# v3-landshark-handheld-controller.net
KiCad netlist of a schematic drawn in EAGLE
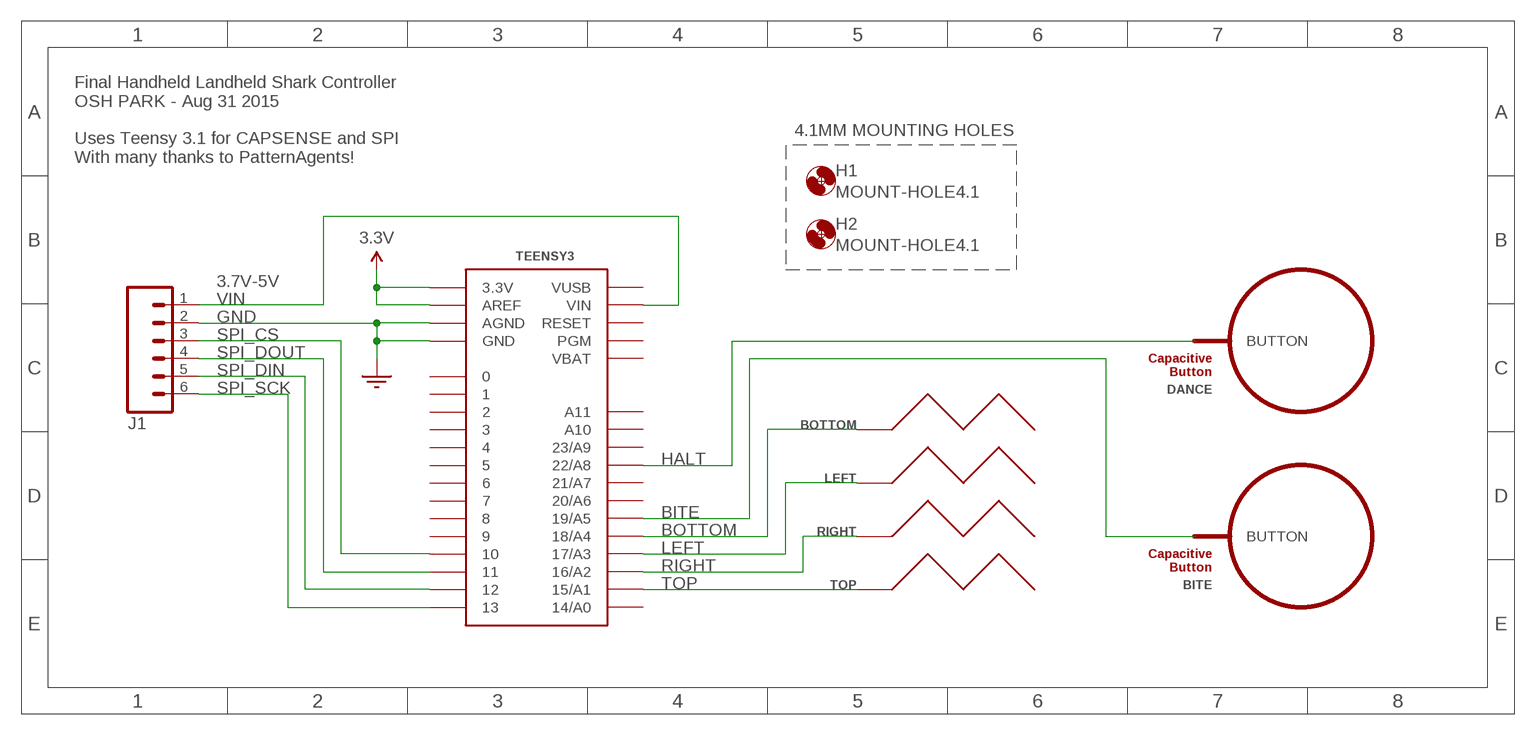
[diagram p0: schematic, sheet 1]

(export (version "E")
  (design (tool "Eeschema 10.0.6"))
  (components
    (comp (ref "BITE")
      (value "BUTTON_PASSIVE_12MM_BITE")
      (footprint "eagle-import:BUTTON_PASSIVE_12MM_BITE")
      (libsource (lib "eagle-import") (part "BUTTON_PASSIVE_12MM_BITE"))
    )
    (comp (ref "BOTTOM")
      (value "SLIDER_PASSIVE_1SEG")
      (footprint "eagle-import:SLIDER_PASSIVE_1SEG_12MM")
      (libsource (lib "eagle-import") (part "SLIDER_PASSIVE_1SEG"))
    )
    (comp (ref "DANCE")
      (value "BUTTON_PASSIVE_12MM_DANCE")
      (footprint "eagle-import:BUTTON_PASSIVE_12MM_DANCE")
      (libsource (lib "eagle-import") (part "BUTTON_PASSIVE_12MM_DANCE"))
    )
    (comp (ref "H1")
      (value "MOUNT-HOLE4.1")
      (footprint "eagle-import:4,1")
      (libsource (lib "eagle-import") (part "MOUNT-HOLE4.1"))
    )
    (comp (ref "H2")
      (value "MOUNT-HOLE4.1")
      (footprint "eagle-import:4,1")
      (libsource (lib "eagle-import") (part "MOUNT-HOLE4.1"))
    )
    (comp (ref "J1")
      (value "M06LOCK_LONGPADS")
      (footprint "eagle-import:1X06_LOCK_LONGPADS")
      (libsource (lib "eagle-import") (part "M06LOCK_LONGPADS"))
    )
    (comp (ref "LEFT")
      (value "SLIDER_PASSIVE_1SEG")
      (footprint "eagle-import:SLIDER_PASSIVE_1SEG_12MM")
      (libsource (lib "eagle-import") (part "SLIDER_PASSIVE_1SEG"))
    )
    (comp (ref "RIGHT")
      (value "SLIDER_PASSIVE_1SEG")
      (footprint "eagle-import:SLIDER_PASSIVE_1SEG_12MM")
      (libsource (lib "eagle-import") (part "SLIDER_PASSIVE_1SEG"))
    )
    (comp (ref "TEENSY3")
      (value "TEENSY_3.0+4")
      (footprint "eagle-import:TEENSY_3.0+4")
      (libsource (lib "eagle-import") (part "TEENSY_3.0+4"))
    )
    (comp (ref "TOP")
      (value "SLIDER_PASSIVE_1SEG")
      (footprint "eagle-import:SLIDER_PASSIVE_1SEG_12MM")
      (libsource (lib "eagle-import") (part "SLIDER_PASSIVE_1SEG"))
    )
  )
  (nets
    (net (code "1") (name "/BITE") (class "Default")
      (node (ref "BITE") (pin "BUTTON") (pinfunction "BUTTON_BUTTON") (pintype "passive"))
      (node (ref "TEENSY3") (pin "19/A5") (pinfunction "19/A5_19/A5") (pintype "bidirectional"))
    )
    (net (code "2") (name "/BOTTOM") (class "Default")
      (node (ref "BOTTOM") (pin "P$1") (pinfunction "SL1_P$1") (pintype "passive"))
      (node (ref "TEENSY3") (pin "18/A4") (pinfunction "18/A4_18/A4") (pintype "bidirectional"))
    )
    (net (code "3") (name "/HALT") (class "Default")
      (node (ref "DANCE") (pin "BUTTON") (pinfunction "BUTTON_BUTTON") (pintype "passive"))
      (node (ref "TEENSY3") (pin "22/A8") (pinfunction "22/A8_22/A8") (pintype "bidirectional"))
    )
    (net (code "4") (name "/LEFT") (class "Default")
      (node (ref "LEFT") (pin "P$1") (pinfunction "SL1_P$1") (pintype "passive"))
      (node (ref "TEENSY3") (pin "17/A3") (pinfunction "17/A3_17/A3") (pintype "bidirectional"))
    )
    (net (code "5") (name "/RIGHT") (class "Default")
      (node (ref "RIGHT") (pin "P$1") (pinfunction "SL1_P$1") (pintype "passive"))
      (node (ref "TEENSY3") (pin "16/A2") (pinfunction "16/A2_16/A2") (pintype "bidirectional"))
    )
    (net (code "6") (name "/SPI_CS") (class "Default")
      (node (ref "J1") (pin "3") (pinfunction "3_3") (pintype "passive"))
      (node (ref "TEENSY3") (pin "10") (pinfunction "10_10") (pintype "bidirectional"))
    )
    (net (code "7") (name "/SPI_DIN") (class "Default")
      (node (ref "J1") (pin "5") (pinfunction "5_5") (pintype "passive"))
      (node (ref "TEENSY3") (pin "12") (pinfunction "12_12") (pintype "bidirectional"))
    )
    (net (code "8") (name "/SPI_DOUT") (class "Default")
      (node (ref "J1") (pin "4") (pinfunction "4_4") (pintype "passive"))
      (node (ref "TEENSY3") (pin "11") (pinfunction "11_11") (pintype "bidirectional"))
    )
    (net (code "9") (name "/SPI_SCK") (class "Default")
      (node (ref "J1") (pin "6") (pinfunction "6_6") (pintype "passive"))
      (node (ref "TEENSY3") (pin "13") (pinfunction "13_13") (pintype "bidirectional"))
    )
    (net (code "10") (name "/TOP") (class "Default")
      (node (ref "TEENSY3") (pin "15/A1") (pinfunction "15/A1_15/A1") (pintype "bidirectional"))
      (node (ref "TOP") (pin "P$1") (pinfunction "SL1_P$1") (pintype "passive"))
    )
    (net (code "11") (name "/VBAT") (class "Default")
      (node (ref "TEENSY3") (pin "VBAT") (pinfunction "VBAT_VBAT") (pintype "power_in"))
    )
    (net (code "12") (name "/VIN") (class "Default")
      (node (ref "J1") (pin "1") (pinfunction "1_1") (pintype "passive"))
      (node (ref "TEENSY3") (pin "VIN") (pinfunction "VIN_VIN") (pintype "power_in"))
    )
    (net (code "13") (name "/VUSB") (class "Default")
      (node (ref "TEENSY3") (pin "VUSB") (pinfunction "VUSB_VUSB") (pintype "power_in"))
    )
    (net (code "14") (name "3.3V") (class "Default")
      (node (ref "TEENSY3") (pin "3.3V") (pinfunction "3.3V_3.3V") (pintype "power_in"))
      (node (ref "TEENSY3") (pin "3.3V1") (pinfunction "3.3V_3.3V1") (pintype "power_in"))
      (node (ref "TEENSY3") (pin "AREF") (pinfunction "AREF_AREF") (pintype "power_in"))
    )
    (net (code "15") (name "GND") (class "Default")
      (node (ref "J1") (pin "2") (pinfunction "2_2") (pintype "passive"))
      (node (ref "TEENSY3") (pin "AGND") (pinfunction "AGND_AGND") (pintype "power_in"))
      (node (ref "TEENSY3") (pin "GND") (pinfunction "GND_GND") (pintype "power_in"))
      (node (ref "TEENSY3") (pin "GND1") (pinfunction "GND_GND1") (pintype "power_in"))
    )
    (net (code "16") (name "unconnected-(TEENSY3-Pad0)") (class "Default")
      (node (ref "TEENSY3") (pin "0") (pinfunction "0_0") (pintype "bidirectional"))
    )
    (net (code "17") (name "unconnected-(TEENSY3-Pad1)") (class "Default")
      (node (ref "TEENSY3") (pin "1") (pinfunction "1_1") (pintype "bidirectional"))
    )
    (net (code "18") (name "unconnected-(TEENSY3-Pad2)") (class "Default")
      (node (ref "TEENSY3") (pin "2") (pinfunction "2_2") (pintype "bidirectional"))
    )
    (net (code "19") (name "unconnected-(TEENSY3-Pad3)") (class "Default")
      (node (ref "TEENSY3") (pin "3") (pinfunction "3_3") (pintype "bidirectional"))
    )
    (net (code "20") (name "unconnected-(TEENSY3-Pad4)") (class "Default")
      (node (ref "TEENSY3") (pin "4") (pinfunction "4_4") (pintype "bidirectional"))
    )
    (net (code "21") (name "unconnected-(TEENSY3-Pad5)") (class "Default")
      (node (ref "TEENSY3") (pin "5") (pinfunction "5_5") (pintype "bidirectional"))
    )
    (net (code "22") (name "unconnected-(TEENSY3-Pad6)") (class "Default")
      (node (ref "TEENSY3") (pin "6") (pinfunction "6_6") (pintype "bidirectional"))
    )
    (net (code "23") (name "unconnected-(TEENSY3-Pad7)") (class "Default")
      (node (ref "TEENSY3") (pin "7") (pinfunction "7_7") (pintype "bidirectional"))
    )
    (net (code "24") (name "unconnected-(TEENSY3-Pad8)") (class "Default")
      (node (ref "TEENSY3") (pin "8") (pinfunction "8_8") (pintype "bidirectional"))
    )
    (net (code "25") (name "unconnected-(TEENSY3-Pad9)") (class "Default")
      (node (ref "TEENSY3") (pin "9") (pinfunction "9_9") (pintype "bidirectional"))
    )
    (net (code "26") (name "unconnected-(TEENSY3-Pad14{slash}A0)") (class "Default")
      (node (ref "TEENSY3") (pin "14/A0") (pinfunction "14/A0_14/A0") (pintype "bidirectional"))
    )
    (net (code "27") (name "unconnected-(TEENSY3-Pad20{slash}A6)") (class "Default")
      (node (ref "TEENSY3") (pin "20/A6") (pinfunction "20/A6_20/A6") (pintype "bidirectional"))
    )
    (net (code "28") (name "unconnected-(TEENSY3-Pad21{slash}A7)") (class "Default")
      (node (ref "TEENSY3") (pin "21/A7") (pinfunction "21/A7_21/A7") (pintype "bidirectional"))
    )
    (net (code "29") (name "unconnected-(TEENSY3-Pad23{slash}A9)") (class "Default")
      (node (ref "TEENSY3") (pin "23/A9") (pinfunction "23/A9_23/A9") (pintype "bidirectional"))
    )
    (net (code "30") (name "unconnected-(TEENSY3-PadA10)") (class "Default")
      (node (ref "TEENSY3") (pin "A10") (pinfunction "A10_A10") (pintype "bidirectional"))
    )
    (net (code "31") (name "unconnected-(TEENSY3-PadA11)") (class "Default")
      (node (ref "TEENSY3") (pin "A11") (pinfunction "A11_A11") (pintype "bidirectional"))
    )
    (net (code "32") (name "unconnected-(TEENSY3-PadPGM)") (class "Default")
      (node (ref "TEENSY3") (pin "PGM") (pinfunction "PGM_PGM") (pintype "bidirectional"))
    )
    (net (code "33") (name "unconnected-(TEENSY3-PadRESET)") (class "Default")
      (node (ref "TEENSY3") (pin "RESET") (pinfunction "RESET_RESET") (pintype "bidirectional"))
    )
  )
)
